# Top_Level_V2.net
KiCad netlist of a schematic drawn in Altium Designer
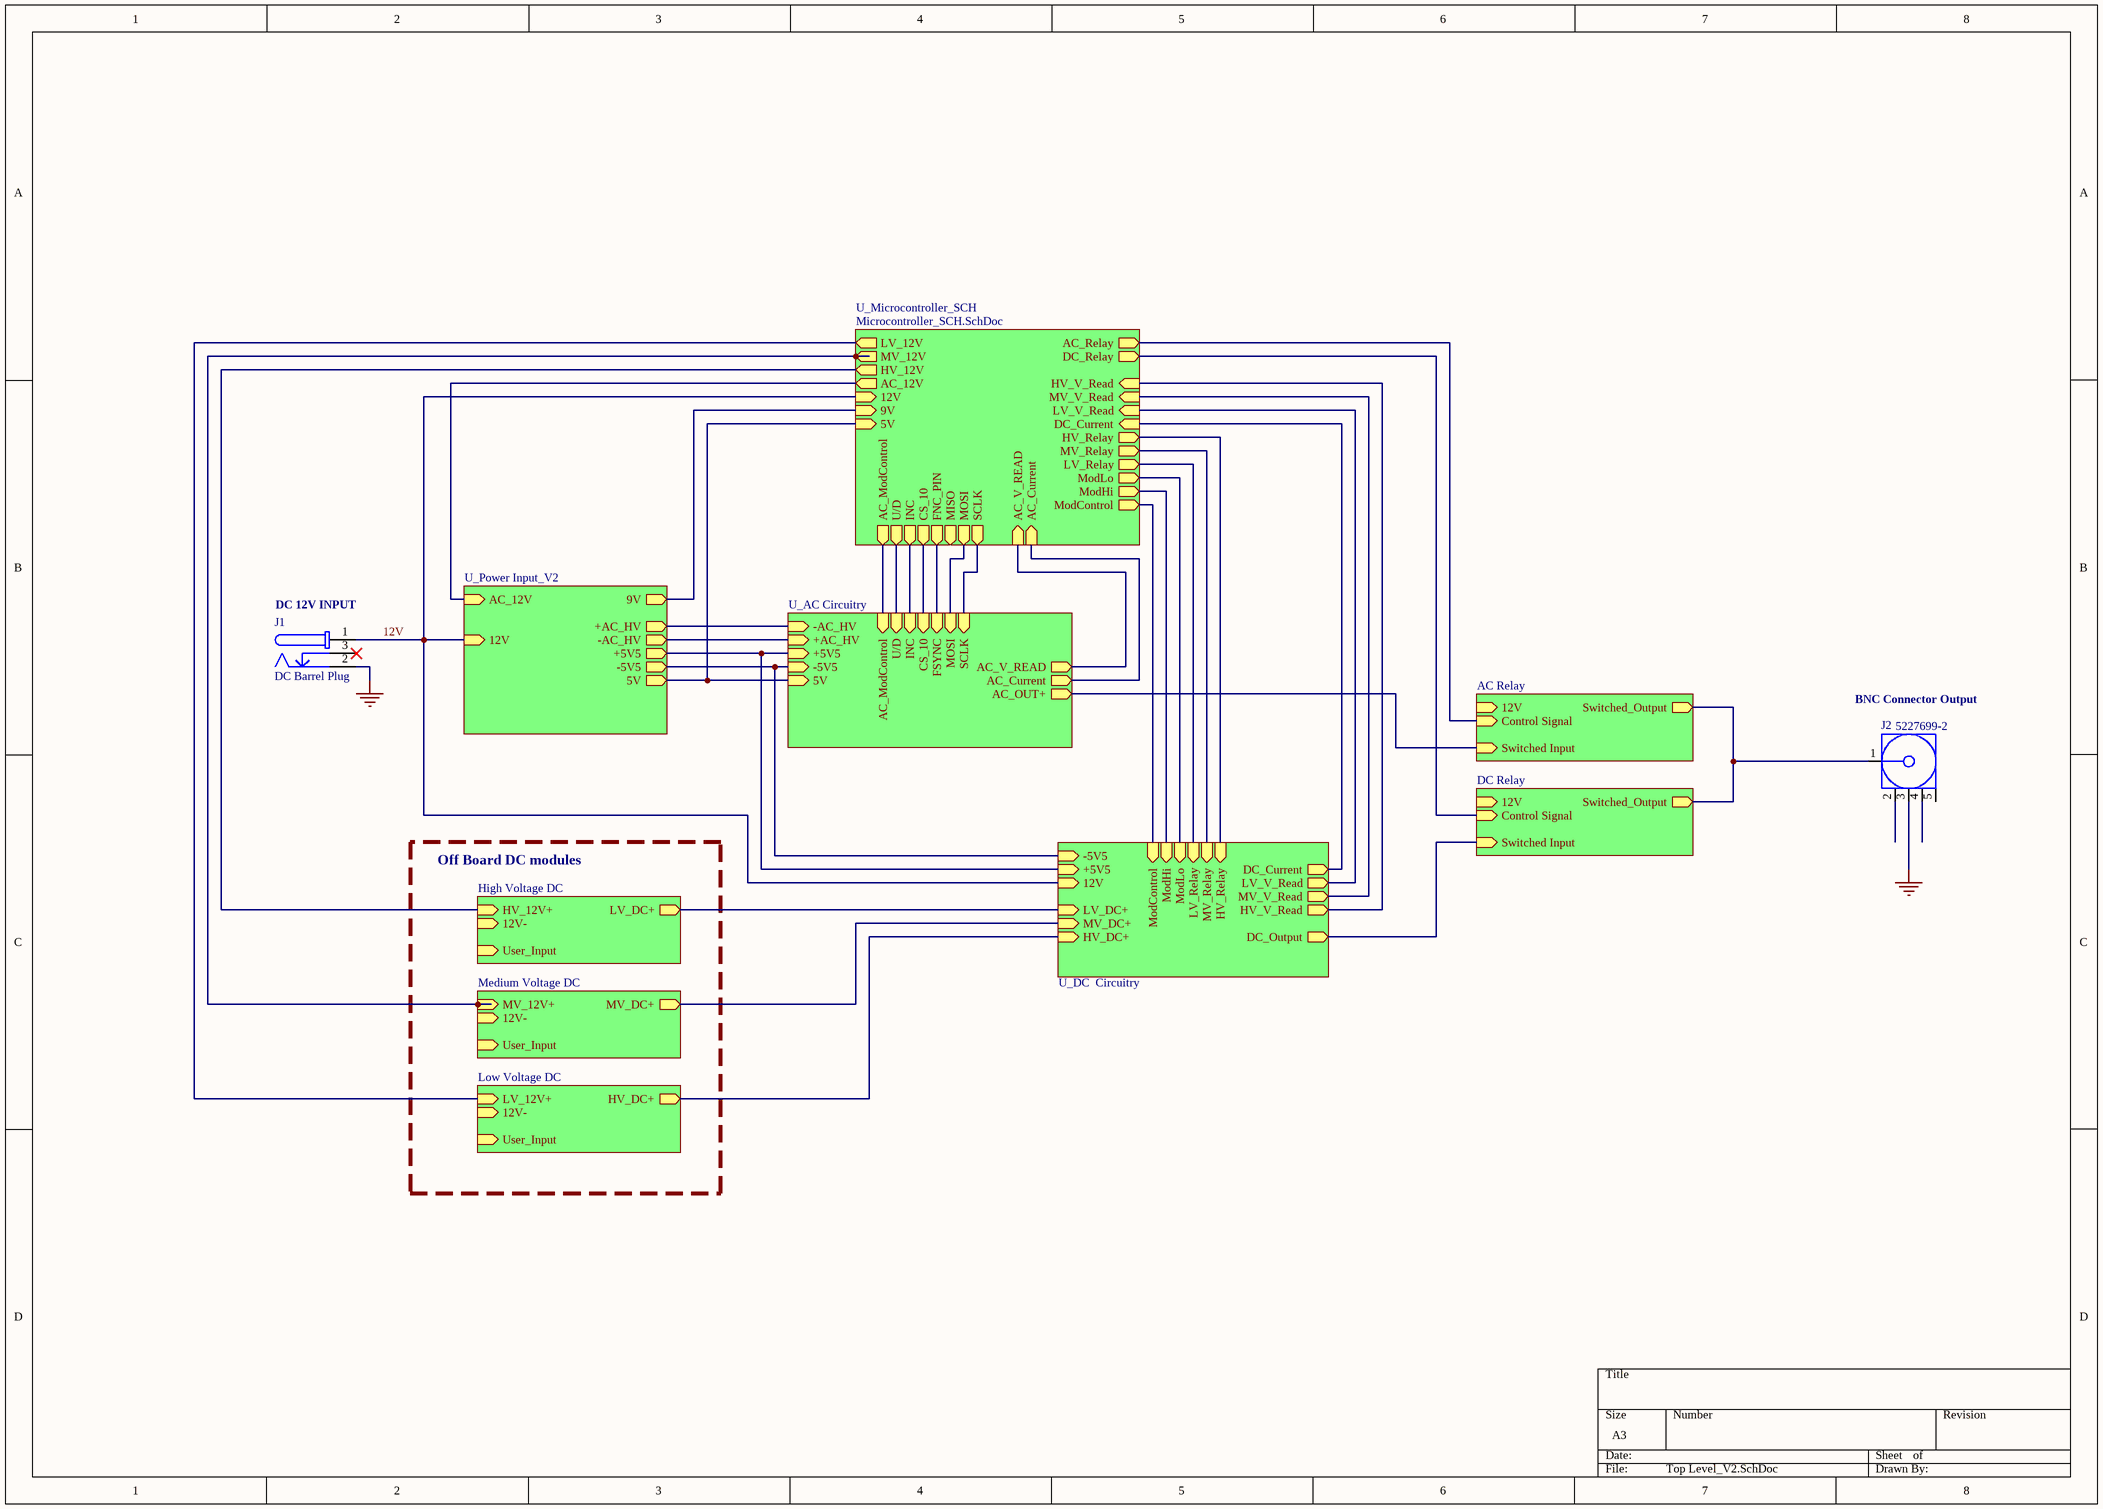
[diagram p0: Top Level_V2.SchDoc]

(export (version "E")
  (design (tool "Eeschema 10.0.6"))
  (components
    (comp (ref "J1")
      (value "DC Barrel Plug")
      (footprint "694108106102")
      (description "24V, 5A, 2.5mm Dia, surface mounted")
      (libsource (lib "University of Western Australia") (part "DC Power Jack"))
    )
    (comp (ref "J2")
      (value "5227699-2")
      (footprint "TECO-5227699-2_V")
      (description "RF BNC Connector, 1 Contact(s), Female, Board Mount, Solder Terminal, Locking, Jack")
      (libsource (lib "University of Western Australia") (part "CN-S-4F-RF5"))
    )
  )
  (nets
    (net (code "7") (name "/12V") (class "Default")
      (node (ref "J1") (pin "1") (pinfunction "1_1") (pintype "passive"))
    )
    (net (code "43") (name "/Switched_Output") (class "Default")
      (node (ref "J2") (pin "1") (pinfunction "1_1") (pintype "passive"))
    )
    (net (code "48") (name "GND") (class "Default")
      (node (ref "J1") (pin "2") (pinfunction "2_2") (pintype "passive"))
      (node (ref "J2") (pin "3") (pinfunction "3_3") (pintype "passive"))
    )
    (net (code "49") (name "unconnected-(J1-Pad3)") (class "Default")
      (node (ref "J1") (pin "3") (pinfunction "3_3") (pintype "passive+no_connect"))
    )
    (net (code "50") (name "unconnected-(J2-Pad2)") (class "Default")
      (node (ref "J2") (pin "2") (pinfunction "2_2") (pintype "passive"))
    )
    (net (code "51") (name "unconnected-(J2-Pad4)") (class "Default")
      (node (ref "J2") (pin "4") (pinfunction "4_4") (pintype "passive"))
    )
    (net (code "52") (name "unconnected-(J2-Pad5)") (class "Default")
      (node (ref "J2") (pin "5") (pinfunction "5_5") (pintype "passive"))
    )
  )
)
